# led.net
KiCad netlist of a schematic drawn in EAGLE
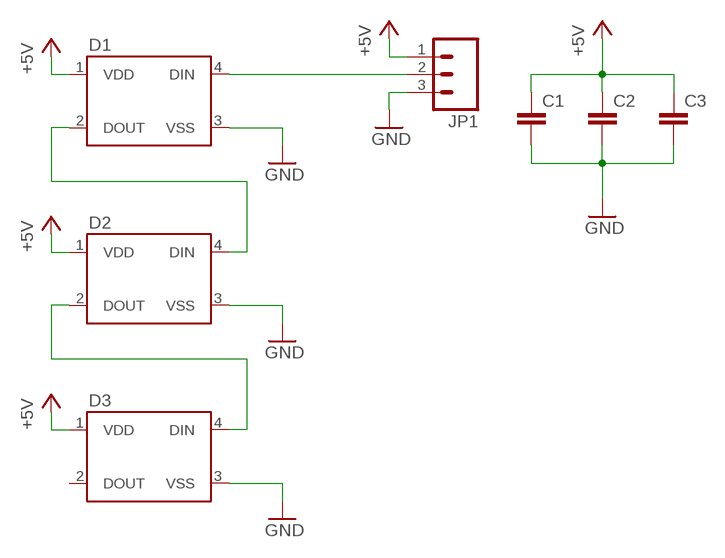
[diagram p0: schematic, sheet 1]

(export (version "E")
  (design (tool "Eeschema 10.0.6"))
  (components
    (comp (ref "C1")
      (value "CAP1206")
      (footprint "eagle-import:1206")
      (libsource (lib "eagle-import") (part "CAP1206"))
    )
    (comp (ref "C2")
      (value "CAP1206")
      (footprint "eagle-import:1206")
      (libsource (lib "eagle-import") (part "CAP1206"))
    )
    (comp (ref "C3")
      (value "CAP1206")
      (footprint "eagle-import:1206")
      (libsource (lib "eagle-import") (part "CAP1206"))
    )
    (comp (ref "D1")
      (value "WS2812B")
      (footprint "eagle-import:WS2812B")
      (libsource (lib "eagle-import") (part "WS2812B"))
    )
    (comp (ref "D2")
      (value "WS2812B")
      (footprint "eagle-import:WS2812B")
      (libsource (lib "eagle-import") (part "WS2812B"))
    )
    (comp (ref "D3")
      (value "WS2812B")
      (footprint "eagle-import:WS2812B")
      (libsource (lib "eagle-import") (part "WS2812B"))
    )
    (comp (ref "JP1")
      (value "M03PTH")
      (footprint "eagle-import:1X03")
      (libsource (lib "eagle-import") (part "M03PTH"))
    )
  )
  (nets
    (net (code "1") (name "+5V") (class "Default")
      (node (ref "C1") (pin "1") (pinfunction "1_1") (pintype "passive"))
      (node (ref "C2") (pin "1") (pinfunction "1_1") (pintype "passive"))
      (node (ref "C3") (pin "1") (pinfunction "1_1") (pintype "passive"))
      (node (ref "D1") (pin "1") (pinfunction "VDD_1") (pintype "power_in"))
      (node (ref "D2") (pin "1") (pinfunction "VDD_1") (pintype "power_in"))
      (node (ref "D3") (pin "1") (pinfunction "VDD_1") (pintype "power_in"))
      (node (ref "JP1") (pin "1") (pinfunction "1_1") (pintype "passive"))
    )
    (net (code "2") (name "GND") (class "Default")
      (node (ref "C1") (pin "2") (pinfunction "2_2") (pintype "passive"))
      (node (ref "C2") (pin "2") (pinfunction "2_2") (pintype "passive"))
      (node (ref "C3") (pin "2") (pinfunction "2_2") (pintype "passive"))
      (node (ref "D1") (pin "3") (pinfunction "VSS_3") (pintype "power_in"))
      (node (ref "D2") (pin "3") (pinfunction "VSS_3") (pintype "power_in"))
      (node (ref "D3") (pin "3") (pinfunction "VSS_3") (pintype "power_in"))
      (node (ref "JP1") (pin "3") (pinfunction "3_3") (pintype "passive"))
    )
    (net (code "3") (name "Net-(D1-DIN)") (class "Default")
      (node (ref "D1") (pin "4") (pinfunction "DIN_4") (pintype "input"))
      (node (ref "JP1") (pin "2") (pinfunction "2_2") (pintype "passive"))
    )
    (net (code "4") (name "Net-(D1-DOUT)") (class "Default")
      (node (ref "D1") (pin "2") (pinfunction "DOUT_2") (pintype "output"))
      (node (ref "D2") (pin "4") (pinfunction "DIN_4") (pintype "input"))
    )
    (net (code "5") (name "Net-(D2-DOUT)") (class "Default")
      (node (ref "D2") (pin "2") (pinfunction "DOUT_2") (pintype "output"))
      (node (ref "D3") (pin "4") (pinfunction "DIN_4") (pintype "input"))
    )
    (net (code "6") (name "unconnected-(D3-DOUT-Pad2)") (class "Default")
      (node (ref "D3") (pin "2") (pinfunction "DOUT_2") (pintype "output"))
    )
  )
)
